# MP3_Testboard.net
KiCad netlist of a schematic drawn in EAGLE
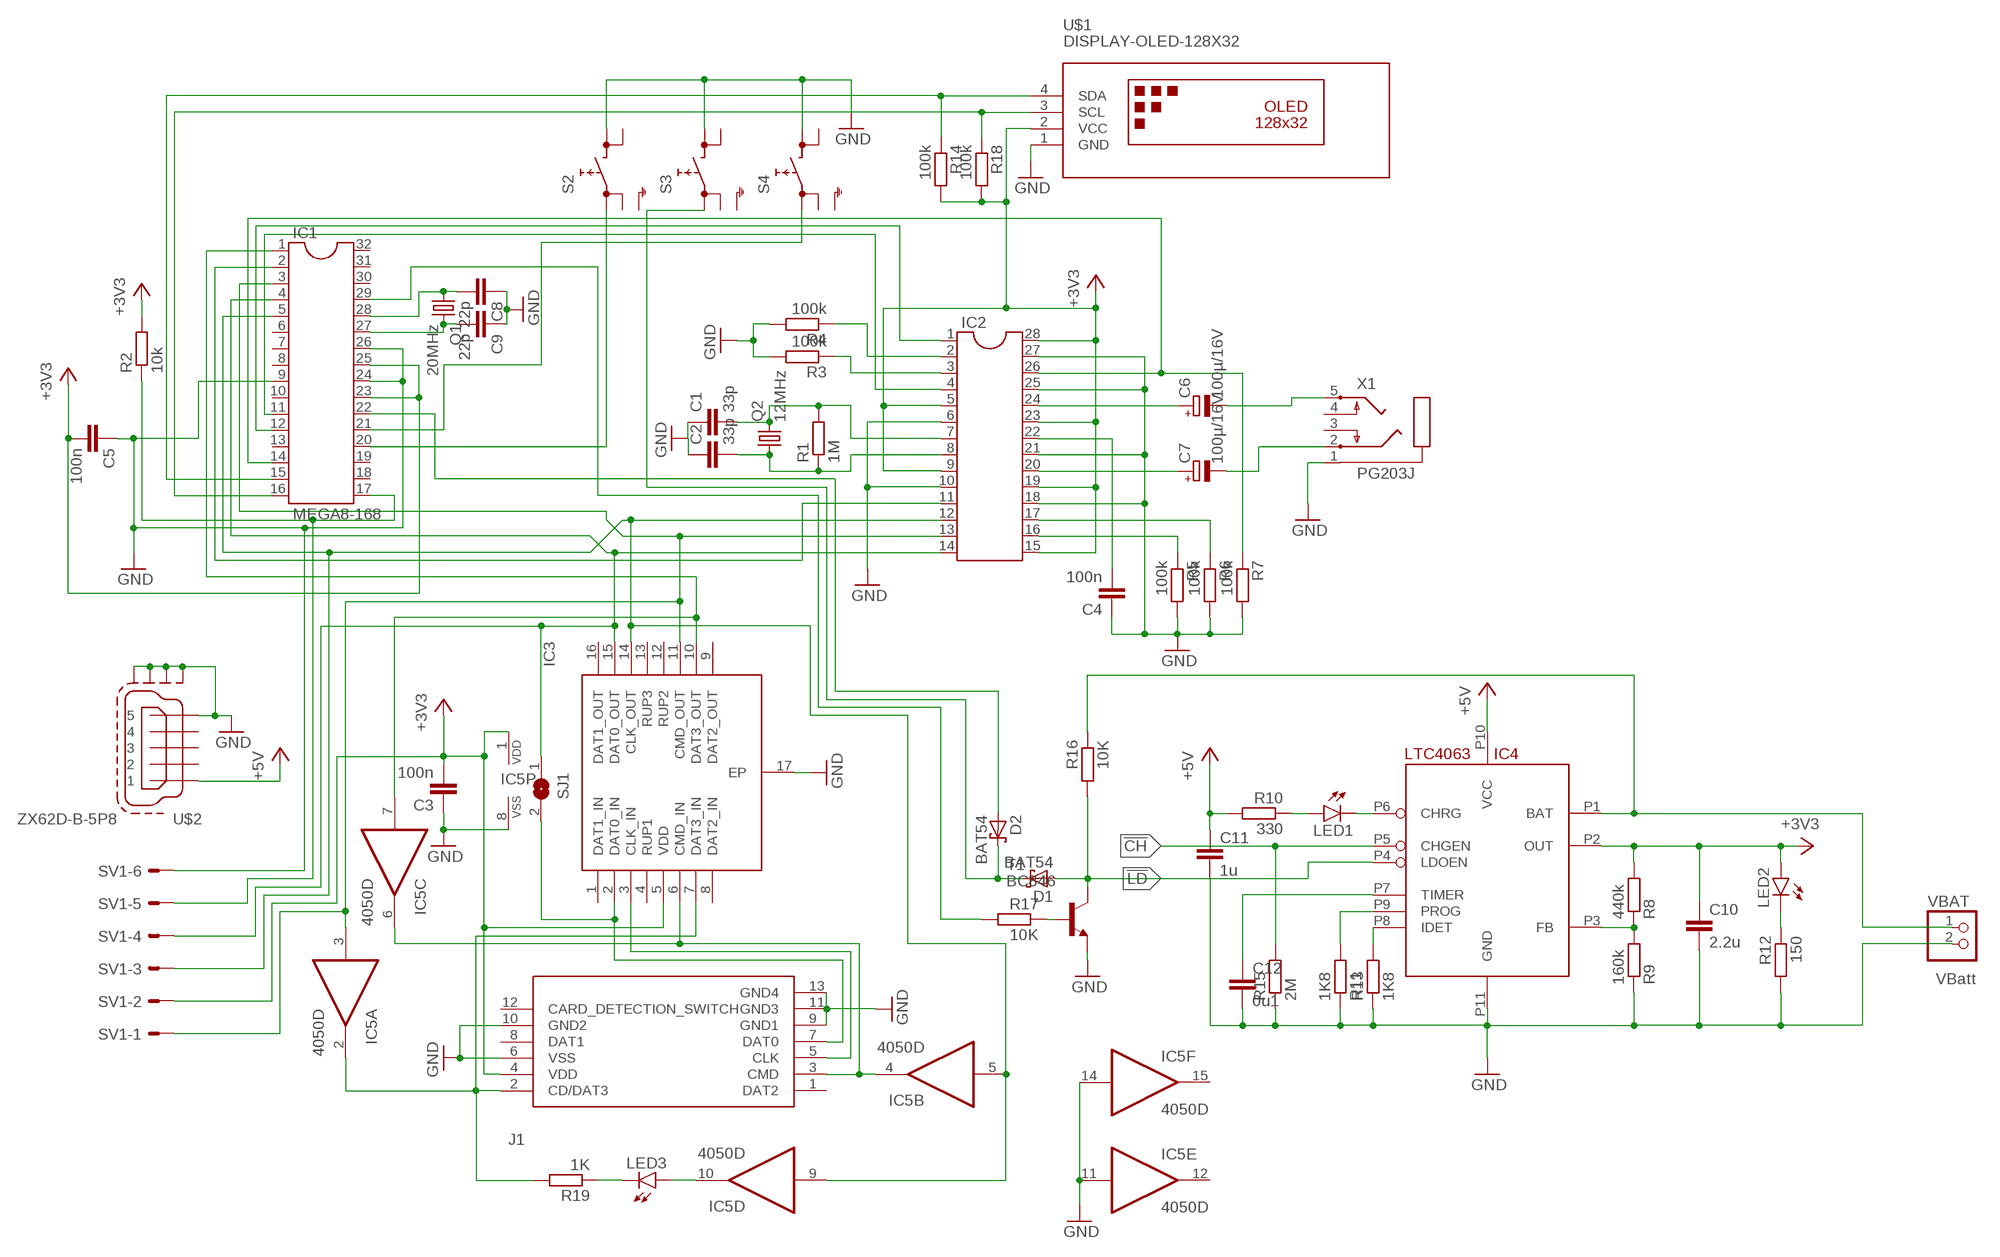
[diagram p0: schematic, sheet 1]

(export (version "E")
  (design (tool "Eeschema 10.0.6"))
  (components
    (comp (ref "C1")
      (value "33p")
      (footprint "eagle-import:C1206K")
      (libsource (lib "eagle-import") (part "C-EUC1206K"))
    )
    (comp (ref "C2")
      (value "33p")
      (footprint "eagle-import:C1206K")
      (libsource (lib "eagle-import") (part "C-EUC1206K"))
    )
    (comp (ref "C3")
      (value "100n")
      (footprint "eagle-import:C1206K")
      (libsource (lib "eagle-import") (part "C-EUC1206K"))
    )
    (comp (ref "C4")
      (value "100n")
      (footprint "eagle-import:C1206K")
      (libsource (lib "eagle-import") (part "C-EUC1206K"))
    )
    (comp (ref "C5")
      (value "100n")
      (footprint "eagle-import:C1206K")
      (libsource (lib "eagle-import") (part "C-EUC1206K"))
    )
    (comp (ref "C6")
      (value "100µ/16V")
      (footprint "eagle-import:UD-6,3X7,7_NICHICON")
      (libsource (lib "eagle-import") (part "CPOL-EUUD-6,3X7,7"))
    )
    (comp (ref "C7")
      (value "100µ/16V")
      (footprint "eagle-import:UD-6,3X7,7_NICHICON")
      (libsource (lib "eagle-import") (part "CPOL-EUUD-6,3X7,7"))
    )
    (comp (ref "C8")
      (value "22p")
      (footprint "eagle-import:C1206K")
      (libsource (lib "eagle-import") (part "rcl_334_C-EUC1206K"))
    )
    (comp (ref "C9")
      (value "22p")
      (footprint "eagle-import:C1206K")
      (libsource (lib "eagle-import") (part "rcl_334_C-EUC1206K"))
    )
    (comp (ref "C10")
      (value "2.2u")
      (footprint "eagle-import:C0805K")
      (libsource (lib "eagle-import") (part "C-EUC0805K"))
    )
    (comp (ref "C11")
      (value "1u")
      (footprint "eagle-import:C0805K")
      (libsource (lib "eagle-import") (part "C-EUC0805K"))
    )
    (comp (ref "C12")
      (value "0u1")
      (footprint "eagle-import:C0805K")
      (libsource (lib "eagle-import") (part "C-EUC0805K"))
    )
    (comp (ref "D1")
      (value "BAT54")
      (footprint "eagle-import:SOT23")
      (libsource (lib "eagle-import") (part "BAT54"))
    )
    (comp (ref "D2")
      (value "BAT54")
      (footprint "eagle-import:SOT23")
      (libsource (lib "eagle-import") (part "BAT54"))
    )
    (comp (ref "IC1")
      (value "MEGA8-168")
      (footprint "eagle-import:DIL32")
      (libsource (lib "eagle-import") (part "DIL32"))
    )
    (comp (ref "IC2")
      (value "DIL28-3")
      (footprint "eagle-import:DIL28-3")
      (libsource (lib "eagle-import") (part "DIL28-3"))
    )
    (comp (ref "IC3")
      (value "ECLAMP2410P.TCT")
      (footprint "eagle-import:SON50P160X400X65-17N")
      (fields (field (name "RS_PART_NUMBER") "6910638"))
      (libsource (lib "eagle-import") (part "ECLAMP2410P.TCT"))
    )
    (comp (ref "IC4")
      (value "LTC4063")
      (footprint "eagle-import:LTC4063")
      (libsource (lib "eagle-import") (part "LTC4063"))
    )
    (comp (ref "IC5")
      (value "4050D")
      (footprint "eagle-import:SO16")
      (libsource (lib "eagle-import") (part "4050D"))
    )
    (comp (ref "J1")
      (value "DM3CS-SF")
      (footprint "eagle-import:DM3CS-SF")
      (fields (field (name "RS_PART_NUMBER") "1664833"))
      (libsource (lib "eagle-import") (part "DM3CS-SF"))
    )
    (comp (ref "LED1")
      (value "LG_T679-E1F1-1")
      (footprint "eagle-import:PLCC2")
      (libsource (lib "eagle-import") (part "_T679-?-1E1F1LG"))
    )
    (comp (ref "LED2")
      (value "LG_T679-E1F1-1")
      (footprint "eagle-import:PLCC2")
      (libsource (lib "eagle-import") (part "_T679-?-1E1F1LG"))
    )
    (comp (ref "LED3")
      (value "LG_T679-E1F1-1")
      (footprint "eagle-import:PLCC2")
      (libsource (lib "eagle-import") (part "_T679-?-1E1F1LG"))
    )
    (comp (ref "Q1")
      (value "20MHz")
      (footprint "eagle-import:HC49UP")
      (libsource (lib "eagle-import") (part "crystal_204_CRYSTALHC49UP"))
    )
    (comp (ref "Q2")
      (value "12MHz")
      (footprint "eagle-import:HC49UP")
      (libsource (lib "eagle-import") (part "CRYSTALHC49UP"))
    )
    (comp (ref "R1")
      (value "1M")
      (footprint "eagle-import:R0805")
      (libsource (lib "eagle-import") (part "rcl_334_R-EU_R0805"))
    )
    (comp (ref "R2")
      (value "10k")
      (footprint "eagle-import:0207_10")
      (libsource (lib "eagle-import") (part "rcl_334_R-EU_0207/10"))
    )
    (comp (ref "R3")
      (value "100k")
      (footprint "eagle-import:R1206")
      (libsource (lib "eagle-import") (part "rcl_334_R-EU_R1206"))
    )
    (comp (ref "R4")
      (value "100k")
      (footprint "eagle-import:R1206")
      (libsource (lib "eagle-import") (part "rcl_334_R-EU_R1206"))
    )
    (comp (ref "R5")
      (value "100k")
      (footprint "eagle-import:R0805")
      (libsource (lib "eagle-import") (part "rcl_334_R-EU_R0805"))
    )
    (comp (ref "R6")
      (value "100k")
      (footprint "eagle-import:R0805")
      (libsource (lib "eagle-import") (part "rcl_334_R-EU_R0805"))
    )
    (comp (ref "R7")
      (value "100k")
      (footprint "eagle-import:R1206")
      (libsource (lib "eagle-import") (part "rcl_334_R-EU_R1206"))
    )
    (comp (ref "R8")
      (value "440k")
      (footprint "eagle-import:R0805")
      (libsource (lib "eagle-import") (part "rcl_334_R-EU_R0805"))
    )
    (comp (ref "R9")
      (value "160k")
      (footprint "eagle-import:R0805")
      (libsource (lib "eagle-import") (part "rcl_334_R-EU_R0805"))
    )
    (comp (ref "R10")
      (value "330")
      (footprint "eagle-import:R0805")
      (libsource (lib "eagle-import") (part "rcl_334_R-EU_R0805"))
    )
    (comp (ref "R11")
      (value "1K8")
      (footprint "eagle-import:R0805")
      (libsource (lib "eagle-import") (part "R-EU_R0805"))
    )
    (comp (ref "R12")
      (value "150")
      (footprint "eagle-import:R0805")
      (libsource (lib "eagle-import") (part "rcl_334_R-EU_R0805"))
    )
    (comp (ref "R13")
      (value "1K8")
      (footprint "eagle-import:R1206")
      (libsource (lib "eagle-import") (part "rcl_334_R-EU_R1206"))
    )
    (comp (ref "R14")
      (value "100k")
      (footprint "eagle-import:R1206")
      (libsource (lib "eagle-import") (part "rcl_334_R-EU_R1206"))
    )
    (comp (ref "R15")
      (value "2M")
      (footprint "eagle-import:R0805")
      (libsource (lib "eagle-import") (part "rcl_334_R-EU_R0805"))
    )
    (comp (ref "R16")
      (value "10K")
      (footprint "eagle-import:0207_10")
      (libsource (lib "eagle-import") (part "rcl_334_R-EU_0207/10"))
    )
    (comp (ref "R17")
      (value "10K")
      (footprint "eagle-import:R0805")
      (libsource (lib "eagle-import") (part "rcl_334_R-EU_R0805"))
    )
    (comp (ref "R18")
      (value "100k")
      (footprint "eagle-import:R1206")
      (libsource (lib "eagle-import") (part "rcl_334_R-EU_R1206"))
    )
    (comp (ref "R19")
      (value "1K")
      (footprint "eagle-import:R1206")
      (libsource (lib "eagle-import") (part "rcl_334_R-EU_R1206"))
    )
    (comp (ref "S2")
      (value "SKHMPSE010")
      (footprint "eagle-import:SKHMPXE010")
      (libsource (lib "eagle-import") (part "SKHMPE010S"))
    )
    (comp (ref "S3")
      (value "SKHMPSE010")
      (footprint "eagle-import:SKHMPXE010")
      (libsource (lib "eagle-import") (part "SKHMPE010S"))
    )
    (comp (ref "S4")
      (value "SKHMPSE010")
      (footprint "eagle-import:SKHMPXE010")
      (libsource (lib "eagle-import") (part "SKHMPE010S"))
    )
    (comp (ref "SJ1") (value "SJ") (footprint "eagle-import:SJ") (libsource (lib "eagle-import") (part "SJ")))
    (comp (ref "SV1")
      (value "ML6E")
      (footprint "eagle-import:ML6")
      (libsource (lib "eagle-import") (part "ML6E"))
    )
    (comp (ref "T1")
      (value "BC846")
      (footprint "eagle-import:SOT23")
      (libsource (lib "eagle-import") (part "BC846"))
    )
    (comp (ref "U$1")
      (value "DISPLAY-OLED-128X32")
      (footprint "eagle-import:DISPLAY-OLED-128X32")
      (libsource (lib "eagle-import") (part "DISPLAY-OLED-128X32"))
    )
    (comp (ref "U$2")
      (value "ZX62D-B-5P8")
      (footprint "eagle-import:ZX62D-B-5P8")
      (libsource (lib "eagle-import") (part "ZX62D-B-5P8"))
    )
    (comp (ref "VBAT")
      (value "PINHD-1X2")
      (footprint "eagle-import:1X02")
      (libsource (lib "eagle-import") (part "PINHD-1X2"))
    )
    (comp (ref "X1")
      (value "PG203J")
      (footprint "eagle-import:PG203J")
      (libsource (lib "eagle-import") (part "PG203J"))
    )
  )
  (nets
    (net (code "1") (name "+3V3") (class "Default")
      (node (ref "C10") (pin "1") (pinfunction "1_1") (pintype "passive"))
      (node (ref "C3") (pin "2") (pinfunction "2_2") (pintype "passive"))
      (node (ref "C5") (pin "2") (pinfunction "2_2") (pintype "passive"))
      (node (ref "IC1") (pin "23") (pinfunction "23_23") (pintype "passive"))
      (node (ref "IC1") (pin "25") (pinfunction "25_25") (pintype "passive"))
      (node (ref "IC2") (pin "15") (pinfunction "15_15") (pintype "passive"))
      (node (ref "IC2") (pin "19") (pinfunction "19_19") (pintype "passive"))
      (node (ref "IC2") (pin "23") (pinfunction "23_23") (pintype "passive"))
      (node (ref "IC2") (pin "28") (pinfunction "28_28") (pintype "passive"))
      (node (ref "IC2") (pin "5") (pinfunction "5_5") (pintype "passive"))
      (node (ref "IC2") (pin "9") (pinfunction "9_9") (pintype "passive"))
      (node (ref "IC3") (pin "5") (pinfunction "VDD_5") (pintype "bidirectional"))
      (node (ref "IC4") (pin "P2") (pinfunction "OUT_P2") (pintype "output"))
      (node (ref "IC5") (pin "1") (pinfunction "VDD_1") (pintype "power_in"))
      (node (ref "J1") (pin "4") (pinfunction "VDD_4") (pintype "bidirectional"))
      (node (ref "LED2") (pin "A") (pinfunction "A_A") (pintype "passive"))
      (node (ref "R14") (pin "2") (pinfunction "2_2") (pintype "passive"))
      (node (ref "R18") (pin "2") (pinfunction "2_2") (pintype "passive"))
      (node (ref "R2") (pin "2") (pinfunction "2_2") (pintype "passive"))
      (node (ref "R8") (pin "2") (pinfunction "2_2") (pintype "passive"))
      (node (ref "SV1") (pin "2") (pinfunction "S_2") (pintype "passive"))
      (node (ref "U$1") (pin "2") (pinfunction "VCC_2") (pintype "power_in"))
    )
    (net (code "2") (name "+5V") (class "Default")
      (node (ref "C11") (pin "1") (pinfunction "1_1") (pintype "passive"))
      (node (ref "IC4") (pin "P10") (pinfunction "VCC_P10") (pintype "power_in"))
      (node (ref "R10") (pin "2") (pinfunction "2_2") (pintype "passive"))
      (node (ref "U$2") (pin "P$1") (pinfunction "1_P$1") (pintype "passive"))
    )
    (net (code "3") (name "/~{CH}") (class "Default")
      (node (ref "IC4") (pin "P5") (pinfunction "CHGEN_P5") (pintype "input"))
      (node (ref "R15") (pin "2") (pinfunction "2_2") (pintype "passive"))
    )
    (net (code "4") (name "/~{LD}") (class "Default")
      (node (ref "D1") (pin "1") (pinfunction "A_1") (pintype "passive"))
      (node (ref "IC4") (pin "P4") (pinfunction "LDOEN_P4") (pintype "input"))
      (node (ref "R16") (pin "2") (pinfunction "2_2") (pintype "passive"))
      (node (ref "T1") (pin "3") (pinfunction "C_3") (pintype "passive"))
    )
    (net (code "5") (name "GND") (class "Default")
      (node (ref "C1") (pin "1") (pinfunction "1_1") (pintype "passive"))
      (node (ref "C10") (pin "2") (pinfunction "2_2") (pintype "passive"))
      (node (ref "C11") (pin "2") (pinfunction "2_2") (pintype "passive"))
      (node (ref "C12") (pin "2") (pinfunction "2_2") (pintype "passive"))
      (node (ref "C2") (pin "1") (pinfunction "1_1") (pintype "passive"))
      (node (ref "C3") (pin "1") (pinfunction "1_1") (pintype "passive"))
      (node (ref "C4") (pin "1") (pinfunction "1_1") (pintype "passive"))
      (node (ref "C5") (pin "1") (pinfunction "1_1") (pintype "passive"))
      (node (ref "C8") (pin "1") (pinfunction "1_1") (pintype "passive"))
      (node (ref "C9") (pin "1") (pinfunction "1_1") (pintype "passive"))
      (node (ref "IC1") (pin "24") (pinfunction "24_24") (pintype "passive"))
      (node (ref "IC1") (pin "26") (pinfunction "26_26") (pintype "passive"))
      (node (ref "IC1") (pin "9") (pinfunction "9_9") (pintype "passive"))
      (node (ref "IC2") (pin "10") (pinfunction "10_10") (pintype "passive"))
      (node (ref "IC2") (pin "18") (pinfunction "18_18") (pintype "passive"))
      (node (ref "IC2") (pin "21") (pinfunction "21_21") (pintype "passive"))
      (node (ref "IC2") (pin "25") (pinfunction "25_25") (pintype "passive"))
      (node (ref "IC2") (pin "27") (pinfunction "27_27") (pintype "passive"))
      (node (ref "IC2") (pin "6") (pinfunction "6_6") (pintype "passive"))
      (node (ref "IC3") (pin "17") (pinfunction "EP_17") (pintype "bidirectional"))
      (node (ref "IC4") (pin "P11") (pinfunction "GND_P11") (pintype "power_in"))
      (node (ref "IC5") (pin "11") (pinfunction "I_11") (pintype "input"))
      (node (ref "IC5") (pin "14") (pinfunction "I_14") (pintype "input"))
      (node (ref "IC5") (pin "8") (pinfunction "VSS_8") (pintype "power_in"))
      (node (ref "J1") (pin "10") (pinfunction "GND2_10") (pintype "bidirectional"))
      (node (ref "J1") (pin "11") (pinfunction "GND3_11") (pintype "bidirectional"))
      (node (ref "J1") (pin "13") (pinfunction "GND4_13") (pintype "bidirectional"))
      (node (ref "J1") (pin "6") (pinfunction "VSS_6") (pintype "bidirectional"))
      (node (ref "J1") (pin "9") (pinfunction "GND1_9") (pintype "bidirectional"))
      (node (ref "R11") (pin "1") (pinfunction "1_1") (pintype "passive"))
      (node (ref "R12") (pin "2") (pinfunction "2_2") (pintype "passive"))
      (node (ref "R13") (pin "1") (pinfunction "1_1") (pintype "passive"))
      (node (ref "R15") (pin "1") (pinfunction "1_1") (pintype "passive"))
      (node (ref "R3") (pin "2") (pinfunction "2_2") (pintype "passive"))
      (node (ref "R4") (pin "2") (pinfunction "2_2") (pintype "passive"))
      (node (ref "R5") (pin "2") (pinfunction "2_2") (pintype "passive"))
      (node (ref "R6") (pin "2") (pinfunction "2_2") (pintype "passive"))
      (node (ref "R7") (pin "2") (pinfunction "2_2") (pintype "passive"))
      (node (ref "R9") (pin "1") (pinfunction "1_1") (pintype "passive"))
      (node (ref "S2") (pin "3") (pinfunction "2.1_3") (pintype "passive"))
      (node (ref "S3") (pin "3") (pinfunction "2.1_3") (pintype "passive"))
      (node (ref "S4") (pin "3") (pinfunction "2.1_3") (pintype "passive"))
      (node (ref "SV1") (pin "6") (pinfunction "S_6") (pintype "passive"))
      (node (ref "T1") (pin "2") (pinfunction "E_2") (pintype "passive"))
      (node (ref "U$1") (pin "1") (pinfunction "GND_1") (pintype "power_in"))
      (node (ref "U$2") (pin "P$5") (pinfunction "5_P$5") (pintype "passive"))
      (node (ref "U$2") (pin "SH1") (pinfunction "SH1_SH1") (pintype "passive"))
      (node (ref "U$2") (pin "SH2") (pinfunction "SH2_SH2") (pintype "passive"))
      (node (ref "U$2") (pin "SH3") (pinfunction "SH3_SH3") (pintype "passive"))
      (node (ref "U$2") (pin "SH4") (pinfunction "SH4_SH4") (pintype "passive"))
      (node (ref "VBAT") (pin "2") (pinfunction "2_2") (pintype "passive"))
      (node (ref "X1") (pin "1") (pinfunction "1_1") (pintype "passive"))
    )
    (net (code "6") (name "Net-(C1-Pad2)") (class "Default")
      (node (ref "C1") (pin "2") (pinfunction "2_2") (pintype "passive"))
      (node (ref "IC2") (pin "7") (pinfunction "7_7") (pintype "passive"))
      (node (ref "Q2") (pin "2") (pinfunction "2_2") (pintype "passive"))
      (node (ref "R1") (pin "2") (pinfunction "2_2") (pintype "passive"))
    )
    (net (code "7") (name "Net-(C2-Pad2)") (class "Default")
      (node (ref "C2") (pin "2") (pinfunction "2_2") (pintype "passive"))
      (node (ref "IC2") (pin "8") (pinfunction "8_8") (pintype "passive"))
      (node (ref "Q2") (pin "1") (pinfunction "1_1") (pintype "passive"))
      (node (ref "R1") (pin "1") (pinfunction "1_1") (pintype "passive"))
    )
    (net (code "8") (name "Net-(C4-Pad2)") (class "Default")
      (node (ref "C4") (pin "2") (pinfunction "2_2") (pintype "passive"))
      (node (ref "IC2") (pin "22") (pinfunction "22_22") (pintype "passive"))
    )
    (net (code "9") (name "Net-(C6-Pad+)") (class "Default")
      (node (ref "C6") (pin "+") (pinfunction "+_+") (pintype "passive"))
      (node (ref "IC2") (pin "24") (pinfunction "24_24") (pintype "passive"))
    )
    (net (code "10") (name "Net-(C6-Pad-)") (class "Default")
      (node (ref "C6") (pin "-") (pinfunction "-_-") (pintype "passive"))
      (node (ref "X1") (pin "5") (pinfunction "5_5") (pintype "passive"))
    )
    (net (code "11") (name "Net-(C7-Pad+)") (class "Default")
      (node (ref "C7") (pin "+") (pinfunction "+_+") (pintype "passive"))
      (node (ref "IC2") (pin "20") (pinfunction "20_20") (pintype "passive"))
    )
    (net (code "12") (name "Net-(C7-Pad-)") (class "Default")
      (node (ref "C7") (pin "-") (pinfunction "-_-") (pintype "passive"))
      (node (ref "X1") (pin "2") (pinfunction "2_2") (pintype "passive"))
    )
    (net (code "13") (name "Net-(C8-Pad2)") (class "Default")
      (node (ref "C8") (pin "2") (pinfunction "2_2") (pintype "passive"))
      (node (ref "IC1") (pin "28") (pinfunction "28_28") (pintype "passive"))
      (node (ref "Q1") (pin "1") (pinfunction "1_1") (pintype "passive"))
    )
    (net (code "14") (name "Net-(C9-Pad2)") (class "Default")
      (node (ref "C9") (pin "2") (pinfunction "2_2") (pintype "passive"))
      (node (ref "IC1") (pin "27") (pinfunction "27_27") (pintype "passive"))
      (node (ref "Q1") (pin "2") (pinfunction "2_2") (pintype "passive"))
    )
    (net (code "15") (name "Net-(D1-C)") (class "Default")
      (node (ref "D1") (pin "3") (pinfunction "C_3") (pintype "passive"))
      (node (ref "D2") (pin "3") (pinfunction "C_3") (pintype "passive"))
      (node (ref "S3") (pin "1") (pinfunction "1.1_1") (pintype "passive"))
    )
    (net (code "16") (name "Net-(D2-A)") (class "Default")
      (node (ref "D2") (pin "1") (pinfunction "A_1") (pintype "passive"))
      (node (ref "IC1") (pin "22") (pinfunction "22_22") (pintype "passive"))
    )
    (net (code "17") (name "Net-(IC1-Pad2)") (class "Default")
      (node (ref "IC1") (pin "2") (pinfunction "2_2") (pintype "passive"))
      (node (ref "IC2") (pin "11") (pinfunction "11_11") (pintype "passive"))
    )
    (net (code "18") (name "Net-(IC1-Pad11)") (class "Default")
      (node (ref "IC1") (pin "11") (pinfunction "11_11") (pintype "passive"))
      (node (ref "IC2") (pin "4") (pinfunction "4_4") (pintype "passive"))
    )
    (net (code "19") (name "Net-(IC1-Pad12)") (class "Default")
      (node (ref "IC1") (pin "12") (pinfunction "12_12") (pintype "passive"))
      (node (ref "IC2") (pin "1") (pinfunction "1_1") (pintype "passive"))
    )
    (net (code "20") (name "Net-(IC1-Pad14)") (class "Default")
      (node (ref "IC1") (pin "14") (pinfunction "14_14") (pintype "passive"))
      (node (ref "IC2") (pin "26") (pinfunction "26_26") (pintype "passive"))
      (node (ref "R7") (pin "1") (pinfunction "1_1") (pintype "passive"))
    )
    (net (code "21") (name "Net-(IC1-Pad29)") (class "Default")
      (node (ref "IC1") (pin "29") (pinfunction "29_29") (pintype "passive"))
      (node (ref "R17") (pin "2") (pinfunction "2_2") (pintype "passive"))
    )
    (net (code "22") (name "Net-(IC2-Pad2)") (class "Default")
      (node (ref "IC2") (pin "2") (pinfunction "2_2") (pintype "passive"))
      (node (ref "R4") (pin "1") (pinfunction "1_1") (pintype "passive"))
    )
    (net (code "23") (name "Net-(IC2-Pad3)") (class "Default")
      (node (ref "IC2") (pin "3") (pinfunction "3_3") (pintype "passive"))
      (node (ref "R3") (pin "1") (pinfunction "1_1") (pintype "passive"))
    )
    (net (code "24") (name "Net-(IC2-Pad16)") (class "Default")
      (node (ref "IC2") (pin "16") (pinfunction "16_16") (pintype "passive"))
      (node (ref "R5") (pin "1") (pinfunction "1_1") (pintype "passive"))
    )
    (net (code "25") (name "Net-(IC2-Pad17)") (class "Default")
      (node (ref "IC2") (pin "17") (pinfunction "17_17") (pintype "passive"))
      (node (ref "R6") (pin "1") (pinfunction "1_1") (pintype "passive"))
    )
    (net (code "26") (name "Net-(IC3-CLK_IN)") (class "Default")
      (node (ref "IC3") (pin "3") (pinfunction "CLK_IN_3") (pintype "bidirectional"))
      (node (ref "J1") (pin "5") (pinfunction "CLK_5") (pintype "bidirectional"))
    )
    (net (code "27") (name "Net-(IC3-CLK_OUT)") (class "Default")
      (node (ref "IC1") (pin "5") (pinfunction "5_5") (pintype "passive"))
      (node (ref "IC2") (pin "12") (pinfunction "12_12") (pintype "passive"))
      (node (ref "IC3") (pin "14") (pinfunction "CLK_OUT_14") (pintype "bidirectional"))
      (node (ref "IC5") (pin "5") (pinfunction "I_5") (pintype "input"))
      (node (ref "IC5") (pin "9") (pinfunction "I_9") (pintype "input"))
      (node (ref "SV1") (pin "3") (pinfunction "S_3") (pintype "passive"))
    )
    (net (code "28") (name "Net-(IC3-CMD_IN)") (class "Default")
      (node (ref "IC3") (pin "6") (pinfunction "CMD_IN_6") (pintype "bidirectional"))
      (node (ref "IC5") (pin "4") (pinfunction "O_4") (pintype "output"))
      (node (ref "IC5") (pin "6") (pinfunction "O_6") (pintype "output"))
      (node (ref "J1") (pin "3") (pinfunction "CMD_3") (pintype "bidirectional"))
    )
    (net (code "29") (name "Net-(IC3-CMD_OUT)") (class "Default")
      (node (ref "IC1") (pin "3") (pinfunction "3_3") (pintype "passive"))
      (node (ref "IC2") (pin "13") (pinfunction "13_13") (pintype "passive"))
      (node (ref "IC3") (pin "11") (pinfunction "CMD_OUT_11") (pintype "bidirectional"))
      (node (ref "IC5") (pin "3") (pinfunction "I_3") (pintype "input"))
      (node (ref "SV1") (pin "1") (pinfunction "S_1") (pintype "passive"))
    )
    (net (code "30") (name "Net-(IC3-DAT0_IN)") (class "Default")
      (node (ref "IC3") (pin "2") (pinfunction "DAT0_IN_2") (pintype "bidirectional"))
      (node (ref "J1") (pin "7") (pinfunction "DAT0_7") (pintype "bidirectional"))
      (node (ref "SJ1") (pin "2") (pinfunction "2_2") (pintype "passive"))
    )
    (net (code "31") (name "Net-(IC3-DAT0_OUT)") (class "Default")
      (node (ref "IC1") (pin "4") (pinfunction "4_4") (pintype "passive"))
      (node (ref "IC2") (pin "14") (pinfunction "14_14") (pintype "passive"))
      (node (ref "IC3") (pin "15") (pinfunction "DAT0_OUT_15") (pintype "bidirectional"))
      (node (ref "SJ1") (pin "1") (pinfunction "1_1") (pintype "passive"))
      (node (ref "SV1") (pin "4") (pinfunction "S_4") (pintype "passive"))
    )
    (net (code "32") (name "Net-(IC3-DAT3_IN)") (class "Default")
      (node (ref "IC3") (pin "7") (pinfunction "DAT3_IN_7") (pintype "bidirectional"))
      (node (ref "IC5") (pin "2") (pinfunction "O_2") (pintype "output"))
      (node (ref "J1") (pin "2") (pinfunction "CD/DAT3_2") (pintype "bidirectional"))
      (node (ref "R19") (pin "2") (pinfunction "2_2") (pintype "passive"))
    )
    (net (code "33") (name "Net-(IC3-DAT3_OUT)") (class "Default")
      (node (ref "IC1") (pin "1") (pinfunction "1_1") (pintype "passive"))
      (node (ref "IC3") (pin "10") (pinfunction "DAT3_OUT_10") (pintype "bidirectional"))
      (node (ref "IC5") (pin "7") (pinfunction "I_7") (pintype "input"))
    )
    (net (code "34") (name "Net-(IC4-BAT)") (class "Default")
      (node (ref "IC4") (pin "P1") (pinfunction "BAT_P1") (pintype "output"))
      (node (ref "R16") (pin "1") (pinfunction "1_1") (pintype "passive"))
      (node (ref "VBAT") (pin "1") (pinfunction "1_1") (pintype "passive"))
    )
    (net (code "35") (name "Net-(IC4-CHRG)") (class "Default")
      (node (ref "IC4") (pin "P6") (pinfunction "CHRG_P6") (pintype "output"))
      (node (ref "LED1") (pin "C") (pinfunction "C_C") (pintype "passive"))
    )
    (net (code "36") (name "Net-(IC4-FB)") (class "Default")
      (node (ref "IC4") (pin "P3") (pinfunction "FB_P3") (pintype "passive"))
      (node (ref "R8") (pin "1") (pinfunction "1_1") (pintype "passive"))
      (node (ref "R9") (pin "2") (pinfunction "2_2") (pintype "passive"))
    )
    (net (code "37") (name "Net-(IC4-IDET)") (class "Default")
      (node (ref "IC4") (pin "P8") (pinfunction "IDET_P8") (pintype "passive"))
      (node (ref "R13") (pin "2") (pinfunction "2_2") (pintype "passive"))
    )
    (net (code "38") (name "Net-(IC4-PROG)") (class "Default")
      (node (ref "IC4") (pin "P9") (pinfunction "PROG_P9") (pintype "passive"))
      (node (ref "R11") (pin "2") (pinfunction "2_2") (pintype "passive"))
    )
    (net (code "39") (name "Net-(IC4-TIMER)") (class "Default")
      (node (ref "C12") (pin "1") (pinfunction "1_1") (pintype "passive"))
      (node (ref "IC4") (pin "P7") (pinfunction "TIMER_P7") (pintype "passive"))
    )
    (net (code "40") (name "Net-(IC5D-O)") (class "Default")
      (node (ref "IC5") (pin "10") (pinfunction "O_10") (pintype "output"))
      (node (ref "LED3") (pin "A") (pinfunction "A_A") (pintype "passive"))
    )
    (net (code "41") (name "Net-(LED1-PadA)") (class "Default")
      (node (ref "LED1") (pin "A") (pinfunction "A_A") (pintype "passive"))
      (node (ref "R10") (pin "1") (pinfunction "1_1") (pintype "passive"))
    )
    (net (code "42") (name "Net-(LED2-PadC)") (class "Default")
      (node (ref "LED2") (pin "C") (pinfunction "C_C") (pintype "passive"))
      (node (ref "R12") (pin "1") (pinfunction "1_1") (pintype "passive"))
    )
    (net (code "43") (name "Net-(LED3-PadC)") (class "Default")
      (node (ref "LED3") (pin "C") (pinfunction "C_C") (pintype "passive"))
      (node (ref "R19") (pin "1") (pinfunction "1_1") (pintype "passive"))
    )
    (net (code "44") (name "Net-(S2-1.1)") (class "Default")
      (node (ref "IC1") (pin "20") (pinfunction "20_20") (pintype "passive"))
      (node (ref "S2") (pin "1") (pinfunction "1.1_1") (pintype "passive"))
    )
    (net (code "45") (name "Net-(S4-1.1)") (class "Default")
      (node (ref "IC1") (pin "21") (pinfunction "21_21") (pintype "passive"))
      (node (ref "S4") (pin "1") (pinfunction "1.1_1") (pintype "passive"))
    )
    (net (code "46") (name "Net-(SV1E-S)") (class "Default")
      (node (ref "IC1") (pin "17") (pinfunction "17_17") (pintype "passive"))
      (node (ref "R2") (pin "1") (pinfunction "1_1") (pintype "passive"))
      (node (ref "SV1") (pin "5") (pinfunction "S_5") (pintype "passive"))
    )
    (net (code "47") (name "Net-(T1-B)") (class "Default")
      (node (ref "R17") (pin "1") (pinfunction "1_1") (pintype "passive"))
      (node (ref "T1") (pin "1") (pinfunction "B_1") (pintype "passive"))
    )
    (net (code "48") (name "Net-(U$1-SCL)") (class "Default")
      (node (ref "IC1") (pin "16") (pinfunction "16_16") (pintype "passive"))
      (node (ref "R18") (pin "1") (pinfunction "1_1") (pintype "passive"))
      (node (ref "U$1") (pin "3") (pinfunction "SCL_3") (pintype "bidirectional"))
    )
    (net (code "49") (name "Net-(U$1-SDA)") (class "Default")
      (node (ref "IC1") (pin "15") (pinfunction "15_15") (pintype "passive"))
      (node (ref "R14") (pin "1") (pinfunction "1_1") (pintype "passive"))
      (node (ref "U$1") (pin "4") (pinfunction "SDA_4") (pintype "bidirectional"))
    )
    (net (code "50") (name "unconnected-(IC1-Pad6)") (class "Default")
      (node (ref "IC1") (pin "6") (pinfunction "6_6") (pintype "passive"))
    )
    (net (code "51") (name "unconnected-(IC1-Pad7)") (class "Default")
      (node (ref "IC1") (pin "7") (pinfunction "7_7") (pintype "passive"))
    )
    (net (code "52") (name "unconnected-(IC1-Pad8)") (class "Default")
      (node (ref "IC1") (pin "8") (pinfunction "8_8") (pintype "passive"))
    )
    (net (code "53") (name "unconnected-(IC1-Pad10)") (class "Default")
      (node (ref "IC1") (pin "10") (pinfunction "10_10") (pintype "passive"))
    )
    (net (code "54") (name "unconnected-(IC1-Pad13)") (class "Default")
      (node (ref "IC1") (pin "13") (pinfunction "13_13") (pintype "passive"))
    )
    (net (code "55") (name "unconnected-(IC1-Pad18)") (class "Default")
      (node (ref "IC1") (pin "18") (pinfunction "18_18") (pintype "passive"))
    )
    (net (code "56") (name "unconnected-(IC1-Pad19)") (class "Default")
      (node (ref "IC1") (pin "19") (pinfunction "19_19") (pintype "passive"))
    )
    (net (code "57") (name "unconnected-(IC1-Pad30)") (class "Default")
      (node (ref "IC1") (pin "30") (pinfunction "30_30") (pintype "passive"))
    )
    (net (code "58") (name "unconnected-(IC1-Pad31)") (class "Default")
      (node (ref "IC1") (pin "31") (pinfunction "31_31") (pintype "passive"))
    )
    (net (code "59") (name "unconnected-(IC1-Pad32)") (class "Default")
      (node (ref "IC1") (pin "32") (pinfunction "32_32") (pintype "passive"))
    )
    (net (code "60") (name "unconnected-(IC3-DAT1_IN-Pad1)") (class "Default")
      (node (ref "IC3") (pin "1") (pinfunction "DAT1_IN_1") (pintype "bidirectional"))
    )
    (net (code "61") (name "unconnected-(IC3-DAT1_OUT-Pad16)") (class "Default")
      (node (ref "IC3") (pin "16") (pinfunction "DAT1_OUT_16") (pintype "bidirectional"))
    )
    (net (code "62") (name "unconnected-(IC3-DAT2_IN-Pad8)") (class "Default")
      (node (ref "IC3") (pin "8") (pinfunction "DAT2_IN_8") (pintype "bidirectional"))
    )
    (net (code "63") (name "unconnected-(IC3-DAT2_OUT-Pad9)") (class "Default")
      (node (ref "IC3") (pin "9") (pinfunction "DAT2_OUT_9") (pintype "bidirectional"))
    )
    (net (code "64") (name "unconnected-(IC3-RUP1-Pad4)") (class "Default")
      (node (ref "IC3") (pin "4") (pinfunction "RUP1_4") (pintype "bidirectional"))
    )
    (net (code "65") (name "unconnected-(IC3-RUP2-Pad12)") (class "Default")
      (node (ref "IC3") (pin "12") (pinfunction "RUP2_12") (pintype "bidirectional"))
    )
    (net (code "66") (name "unconnected-(IC3-RUP3-Pad13)") (class "Default")
      (node (ref "IC3") (pin "13") (pinfunction "RUP3_13") (pintype "bidirectional"))
    )
    (net (code "67") (name "unconnected-(IC5E-O-Pad12)") (class "Default")
      (node (ref "IC5") (pin "12") (pinfunction "O_12") (pintype "output"))
    )
    (net (code "68") (name "unconnected-(IC5F-O-Pad15)") (class "Default")
      (node (ref "IC5") (pin "15") (pinfunction "O_15") (pintype "output"))
    )
    (net (code "69") (name "unconnected-(J1-CARD_DETECTION_SWITCH-Pad12)") (class "Default")
      (node (ref "J1") (pin "12") (pinfunction "CARD_DETECTION_SWITCH_12") (pintype "bidirectional"))
    )
    (net (code "70") (name "unconnected-(J1-DAT1-Pad8)") (class "Default")
      (node (ref "J1") (pin "8") (pinfunction "DAT1_8") (pintype "bidirectional"))
    )
    (net (code "71") (name "unconnected-(J1-DAT2-Pad1)") (class "Default")
      (node (ref "J1") (pin "1") (pinfunction "DAT2_1") (pintype "bidirectional"))
    )
    (net (code "72") (name "unconnected-(S2-1.2-Pad2)") (class "Default")
      (node (ref "S2") (pin "2") (pinfunction "1.2_2") (pintype "passive"))
    )
    (net (code "73") (name "unconnected-(S2-2.2-Pad4)") (class "Default")
      (node (ref "S2") (pin "4") (pinfunction "2.2_4") (pintype "passive"))
    )
    (net (code "74") (name "unconnected-(S2-SH-Pad5)") (class "Default")
      (node (ref "S2") (pin "5") (pinfunction "SH_5") (pintype "passive"))
    )
    (net (code "75") (name "unconnected-(S3-1.2-Pad2)") (class "Default")
      (node (ref "S3") (pin "2") (pinfunction "1.2_2") (pintype "passive"))
    )
    (net (code "76") (name "unconnected-(S3-2.2-Pad4)") (class "Default")
      (node (ref "S3") (pin "4") (pinfunction "2.2_4") (pintype "passive"))
    )
    (net (code "77") (name "unconnected-(S3-SH-Pad5)") (class "Default")
      (node (ref "S3") (pin "5") (pinfunction "SH_5") (pintype "passive"))
    )
    (net (code "78") (name "unconnected-(S4-1.2-Pad2)") (class "Default")
      (node (ref "S4") (pin "2") (pinfunction "1.2_2") (pintype "passive"))
    )
    (net (code "79") (name "unconnected-(S4-2.2-Pad4)") (class "Default")
      (node (ref "S4") (pin "4") (pinfunction "2.2_4") (pintype "passive"))
    )
    (net (code "80") (name "unconnected-(S4-SH-Pad5)") (class "Default")
      (node (ref "S4") (pin "5") (pinfunction "SH_5") (pintype "passive"))
    )
    (net (code "81") (name "unconnected-(U$2-2-PadP$2)") (class "Default")
      (node (ref "U$2") (pin "P$2") (pinfunction "2_P$2") (pintype "passive"))
    )
    (net (code "82") (name "unconnected-(U$2-3-PadP$3)") (class "Default")
      (node (ref "U$2") (pin "P$3") (pinfunction "3_P$3") (pintype "passive"))
    )
    (net (code "83") (name "unconnected-(U$2-4-PadP$4)") (class "Default")
      (node (ref "U$2") (pin "P$4") (pinfunction "4_P$4") (pintype "passive"))
    )
    (net (code "84") (name "unconnected-(X1-Pad3)") (class "Default")
      (node (ref "X1") (pin "3") (pinfunction "3_3") (pintype "passive"))
    )
    (net (code "85") (name "unconnected-(X1-Pad4)") (class "Default")
      (node (ref "X1") (pin "4") (pinfunction "4_4") (pintype "passive"))
    )
  )
)
